# Motorcontroller.net
KiCad netlist of a schematic drawn in EAGLE
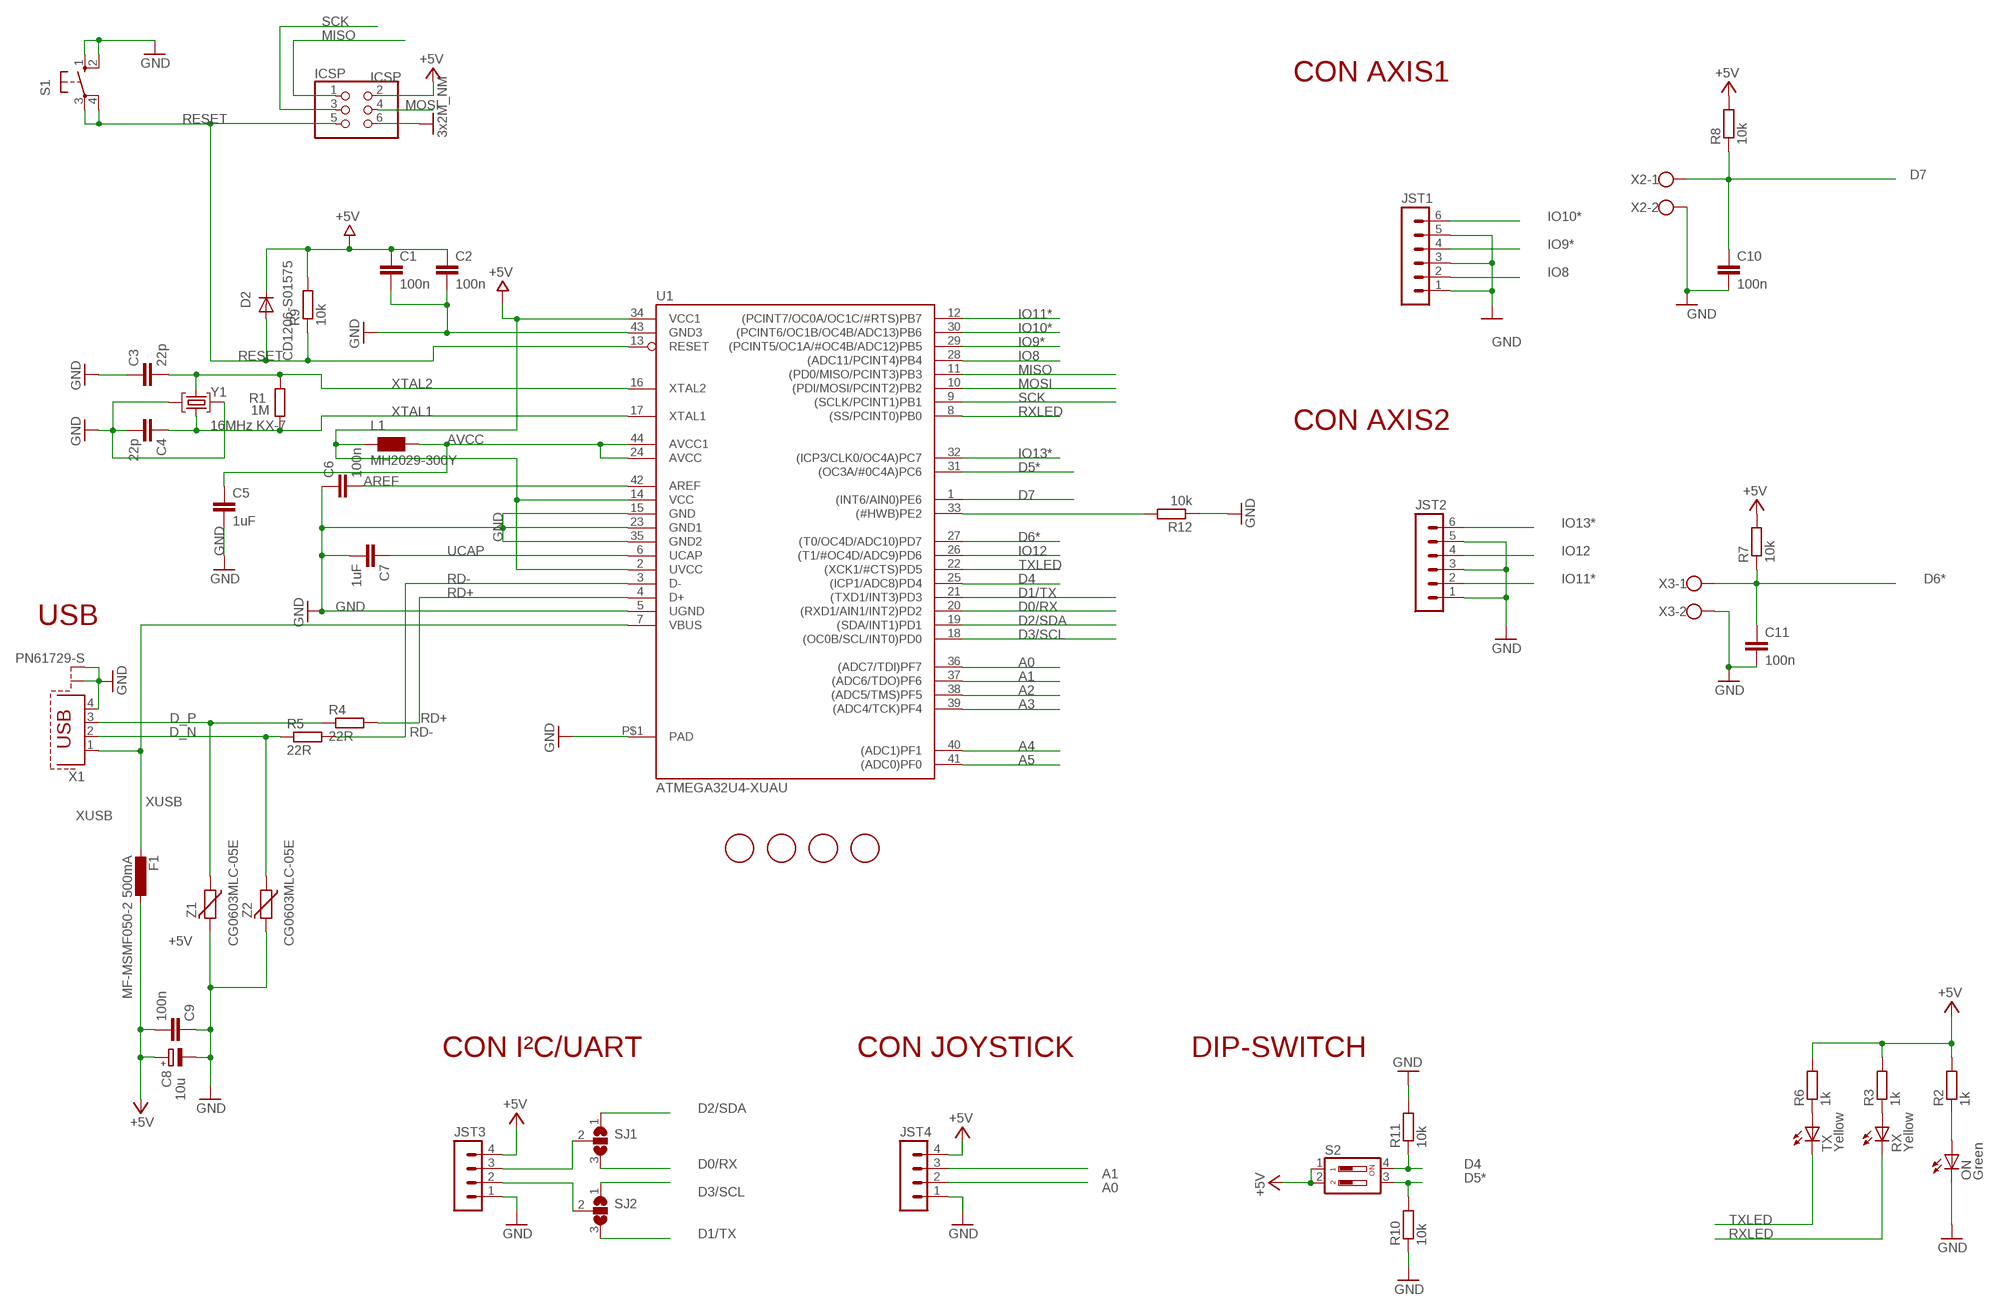
[diagram p0: schematic, sheet 1]

(export (version "E")
  (design (tool "Eeschema 10.0.6"))
  (components
    (comp (ref "C1")
      (value "100n")
      (footprint "eagle-import:C0805")
      (libsource (lib "eagle-import") (part "C-EUC0805"))
    )
    (comp (ref "C2")
      (value "100n")
      (footprint "eagle-import:C0805")
      (libsource (lib "eagle-import") (part "C-EUC0805"))
    )
    (comp (ref "C3")
      (value "22p")
      (footprint "eagle-import:C0805")
      (libsource (lib "eagle-import") (part "C-EUC0805"))
    )
    (comp (ref "C4")
      (value "22p")
      (footprint "eagle-import:C0805")
      (libsource (lib "eagle-import") (part "C-EUC0805"))
    )
    (comp (ref "C5")
      (value "1uF")
      (footprint "eagle-import:C0805")
      (libsource (lib "eagle-import") (part "C-EUC0805"))
    )
    (comp (ref "C6")
      (value "100n")
      (footprint "eagle-import:C0805")
      (libsource (lib "eagle-import") (part "C-EUC0805"))
    )
    (comp (ref "C7")
      (value "1uF")
      (footprint "eagle-import:C0805")
      (libsource (lib "eagle-import") (part "C-EUC0805"))
    )
    (comp (ref "C8")
      (value "10u")
      (footprint "eagle-import:SMC_B")
      (libsource (lib "eagle-import") (part "CPOL-EUSMCB"))
    )
    (comp (ref "C9")
      (value "100n")
      (footprint "eagle-import:C0805")
      (libsource (lib "eagle-import") (part "C-EUC0805"))
    )
    (comp (ref "C10")
      (value "100n")
      (footprint "eagle-import:C0805")
      (libsource (lib "eagle-import") (part "rcl_334_C-EUC0805"))
    )
    (comp (ref "C11")
      (value "100n")
      (footprint "eagle-import:C0805")
      (libsource (lib "eagle-import") (part "rcl_334_C-EUC0805"))
    )
    (comp (ref "D2")
      (value "CD1206-S01575")
      (footprint "eagle-import:MINIMELF")
      (libsource (lib "eagle-import") (part "DIODE-MINIMELF"))
    )
    (comp (ref "F1")
      (value "MF-MSMF050-2 500mA")
      (footprint "eagle-import:L1812")
      (libsource (lib "eagle-import") (part "L-EUL1812"))
    )
    (comp (ref "FID1")
      (value "FIDUCIALMOUNT")
      (footprint "eagle-import:FIDUCIA-MOUNT")
      (libsource (lib "eagle-import") (part "FIDUCIALMOUNT"))
    )
    (comp (ref "FID2")
      (value "FIDUCIALMOUNT")
      (footprint "eagle-import:FIDUCIA-MOUNT")
      (libsource (lib "eagle-import") (part "FIDUCIALMOUNT"))
    )
    (comp (ref "FID3")
      (value "FIDUCIALMOUNT")
      (footprint "eagle-import:FIDUCIA-MOUNT")
      (libsource (lib "eagle-import") (part "FIDUCIALMOUNT"))
    )
    (comp (ref "FID4")
      (value "FIDUCIALMOUNT")
      (footprint "eagle-import:FIDUCIA-MOUNT")
      (libsource (lib "eagle-import") (part "FIDUCIALMOUNT"))
    )
    (comp (ref "ICSP")
      (value "ICSP")
      (footprint "eagle-import:2X03")
      (libsource (lib "eagle-import") (part "PINHD-2X3"))
    )
    (comp (ref "JST1")
      (value "MA06-1")
      (footprint "eagle-import:MA06-1")
      (libsource (lib "eagle-import") (part "MA06-1"))
    )
    (comp (ref "JST2")
      (value "MA06-1")
      (footprint "eagle-import:MA06-1")
      (libsource (lib "eagle-import") (part "MA06-1"))
    )
    (comp (ref "JST3")
      (value "MA04-1")
      (footprint "eagle-import:MA04-1")
      (libsource (lib "eagle-import") (part "MA04-1"))
    )
    (comp (ref "JST4")
      (value "MA04-1")
      (footprint "eagle-import:MA04-1")
      (libsource (lib "eagle-import") (part "MA04-1"))
    )
    (comp (ref "L1")
      (value "MH2029-300Y")
      (footprint "eagle-import:0805")
      (libsource (lib "eagle-import") (part "WE-CBF_0805"))
    )
    (comp (ref "ON")
      (value "Green")
      (footprint "eagle-import:CHIPLED_0805")
      (libsource (lib "eagle-import") (part "LEDCHIPLED_0805"))
    )
    (comp (ref "R1")
      (value "1M")
      (footprint "eagle-import:R0805")
      (libsource (lib "eagle-import") (part "R-EU_R0805"))
    )
    (comp (ref "R2")
      (value "1k")
      (footprint "eagle-import:R0805")
      (libsource (lib "eagle-import") (part "rcl_334_R-EU_R0805"))
    )
    (comp (ref "R3")
      (value "1k")
      (footprint "eagle-import:R0805")
      (libsource (lib "eagle-import") (part "rcl_334_R-EU_R0805"))
    )
    (comp (ref "R4")
      (value "22R")
      (footprint "eagle-import:R0805")
      (libsource (lib "eagle-import") (part "rcl_334_R-EU_R0805"))
    )
    (comp (ref "R5")
      (value "22R")
      (footprint "eagle-import:R0805")
      (libsource (lib "eagle-import") (part "rcl_334_R-EU_R0805"))
    )
    (comp (ref "R6")
      (value "1k")
      (footprint "eagle-import:R0805")
      (libsource (lib "eagle-import") (part "rcl_334_R-EU_R0805"))
    )
    (comp (ref "R7")
      (value "10k")
      (footprint "eagle-import:R0805")
      (libsource (lib "eagle-import") (part "rcl_334_R-EU_R0805"))
    )
    (comp (ref "R8")
      (value "10k")
      (footprint "eagle-import:R0805")
      (libsource (lib "eagle-import") (part "rcl_334_R-EU_R0805"))
    )
    (comp (ref "R9")
      (value "10k")
      (footprint "eagle-import:R0805")
      (libsource (lib "eagle-import") (part "rcl_334_R-EU_R0805"))
    )
    (comp (ref "R10")
      (value "10k")
      (footprint "eagle-import:R0805")
      (libsource (lib "eagle-import") (part "rcl_334_R-EU_R0805"))
    )
    (comp (ref "R11")
      (value "10k")
      (footprint "eagle-import:R0805")
      (libsource (lib "eagle-import") (part "rcl_334_R-EU_R0805"))
    )
    (comp (ref "R12")
      (value "10k")
      (footprint "eagle-import:R0805")
      (libsource (lib "eagle-import") (part "rcl_334_R-EU_R0805"))
    )
    (comp (ref "RX")
      (value "Yellow")
      (footprint "eagle-import:CHIPLED_0805")
      (libsource (lib "eagle-import") (part "LEDCHIPLED_0805"))
    )
    (comp (ref "S1")
      (value "10-XX")
      (footprint "eagle-import:B3F-10XX")
      (fields (field (name "MPN") "B3F-1000"))
      (libsource (lib "eagle-import") (part "10-XX"))
    )
    (comp (ref "S2")
      (value "DIP02YL")
      (footprint "eagle-import:DIP02YL")
      (libsource (lib "eagle-import") (part "DIP02YL"))
    )
    (comp (ref "SJ1")
      (value "SJ2W")
      (footprint "eagle-import:SJ_2")
      (libsource (lib "eagle-import") (part "SJ2W"))
    )
    (comp (ref "SJ2")
      (value "SJ2W")
      (footprint "eagle-import:SJ_2")
      (libsource (lib "eagle-import") (part "SJ2W"))
    )
    (comp (ref "TX")
      (value "Yellow")
      (footprint "eagle-import:CHIPLED_0805")
      (libsource (lib "eagle-import") (part "LEDCHIPLED_0805"))
    )
    (comp (ref "U1")
      (value "ATMEGA32U4-XUAU")
      (footprint "eagle-import:TQFP44-PAD")
      (libsource (lib "eagle-import") (part "ATMEGA32U4-XUAU"))
    )
    (comp (ref "X1")
      (value "PN61729-S")
      (footprint "eagle-import:PN61729-S")
      (libsource (lib "eagle-import") (part "PN61729-S"))
    )
    (comp (ref "X2")
      (value "W237-102")
      (footprint "eagle-import:W237-102")
      (fields (field (name "MPN") "237-102"))
      (libsource (lib "eagle-import") (part "W237-102"))
    )
    (comp (ref "X3")
      (value "W237-102")
      (footprint "eagle-import:W237-102")
      (fields (field (name "MPN") "237-102"))
      (libsource (lib "eagle-import") (part "W237-102"))
    )
    (comp (ref "Y1")
      (value "16MHz KX-7")
      (footprint "eagle-import:CRYSTAL-3.2-2.5")
      (libsource (lib "eagle-import") (part "CRYSTAL-3.2-2.5"))
    )
    (comp (ref "Z1")
      (value "CG0603MLC-05E")
      (footprint "eagle-import:CT_CN0805")
      (libsource (lib "eagle-import") (part "VARISTORCN0805"))
    )
    (comp (ref "Z2")
      (value "CG0603MLC-05E")
      (footprint "eagle-import:CT_CN0805")
      (libsource (lib "eagle-import") (part "VARISTORCN0805"))
    )
  )
  (nets
    (net (code "1") (name "+5V") (class "Default")
      (node (ref "C1") (pin "1") (pinfunction "1_1") (pintype "passive"))
      (node (ref "C2") (pin "1") (pinfunction "1_1") (pintype "passive"))
      (node (ref "C8") (pin "+") (pinfunction "+_+") (pintype "passive"))
      (node (ref "C9") (pin "2") (pinfunction "2_2") (pintype "passive"))
      (node (ref "D2") (pin "C") (pinfunction "C_C") (pintype "passive"))
      (node (ref "F1") (pin "1") (pinfunction "1_1") (pintype "passive"))
      (node (ref "ICSP") (pin "2") (pinfunction "2_2") (pintype "passive"))
      (node (ref "JST3") (pin "4") (pinfunction "4_4") (pintype "passive"))
      (node (ref "JST4") (pin "4") (pinfunction "4_4") (pintype "passive"))
      (node (ref "L1") (pin "1") (pinfunction "1_1") (pintype "passive"))
      (node (ref "R2") (pin "2") (pinfunction "2_2") (pintype "passive"))
      (node (ref "R3") (pin "2") (pinfunction "2_2") (pintype "passive"))
      (node (ref "R6") (pin "2") (pinfunction "2_2") (pintype "passive"))
      (node (ref "R7") (pin "2") (pinfunction "2_2") (pintype "passive"))
      (node (ref "R8") (pin "2") (pinfunction "2_2") (pintype "passive"))
      (node (ref "R9") (pin "2") (pinfunction "2_2") (pintype "passive"))
      (node (ref "S2") (pin "1") (pinfunction "1_1") (pintype "passive"))
      (node (ref "S2") (pin "2") (pinfunction "2_2") (pintype "passive"))
      (node (ref "U1") (pin "14") (pinfunction "VCC_14") (pintype "power_in"))
      (node (ref "U1") (pin "2") (pinfunction "UVCC_2") (pintype "power_in"))
      (node (ref "U1") (pin "34") (pinfunction "VCC1_34") (pintype "power_in"))
    )
    (net (code "2") (name "/A0") (class "Default")
      (node (ref "JST4") (pin "2") (pinfunction "2_2") (pintype "passive"))
      (node (ref "U1") (pin "36") (pinfunction "(ADC7/TDI)PF7_36") (pintype "bidirectional"))
    )
    (net (code "3") (name "/A1") (class "Default")
      (node (ref "JST4") (pin "3") (pinfunction "3_3") (pintype "passive"))
      (node (ref "U1") (pin "37") (pinfunction "(ADC6/TDO)PF6_37") (pintype "bidirectional"))
    )
    (net (code "4") (name "/A2") (class "Default")
      (node (ref "U1") (pin "38") (pinfunction "(ADC5/TMS)PF5_38") (pintype "bidirectional"))
    )
    (net (code "5") (name "/A3") (class "Default")
      (node (ref "U1") (pin "39") (pinfunction "(ADC4/TCK)PF4_39") (pintype "bidirectional"))
    )
    (net (code "6") (name "/A4") (class "Default")
      (node (ref "U1") (pin "40") (pinfunction "(ADC1)PF1_40") (pintype "bidirectional"))
    )
    (net (code "7") (name "/A5") (class "Default")
      (node (ref "U1") (pin "41") (pinfunction "(ADC0)PF0_41") (pintype "bidirectional"))
    )
    (net (code "8") (name "/AREF") (class "Default")
      (node (ref "C6") (pin "2") (pinfunction "2_2") (pintype "passive"))
      (node (ref "U1") (pin "42") (pinfunction "AREF_42") (pintype "power_in"))
    )
    (net (code "9") (name "/AVCC") (class "Default")
      (node (ref "C5") (pin "1") (pinfunction "1_1") (pintype "passive"))
      (node (ref "L1") (pin "2") (pinfunction "2_2") (pintype "passive"))
      (node (ref "U1") (pin "24") (pinfunction "AVCC_24") (pintype "power_in"))
      (node (ref "U1") (pin "44") (pinfunction "AVCC1_44") (pintype "power_in"))
    )
    (net (code "10") (name "/D0{slash}RX") (class "Default")
      (node (ref "SJ1") (pin "3") (pinfunction "3_3") (pintype "passive"))
      (node (ref "U1") (pin "20") (pinfunction "(RXD1/AIN1/INT2)PD2_20") (pintype "bidirectional"))
    )
    (net (code "11") (name "/D1{slash}TX") (class "Default")
      (node (ref "SJ2") (pin "3") (pinfunction "3_3") (pintype "passive"))
      (node (ref "U1") (pin "21") (pinfunction "(TXD1/INT3)PD3_21") (pintype "bidirectional"))
    )
    (net (code "12") (name "/D2{slash}SDA") (class "Default")
      (node (ref "SJ1") (pin "1") (pinfunction "1_1") (pintype "passive"))
      (node (ref "U1") (pin "19") (pinfunction "(SDA/INT1)PD1_19") (pintype "bidirectional"))
    )
    (net (code "13") (name "/D3{slash}SCL") (class "Default")
      (node (ref "SJ2") (pin "1") (pinfunction "1_1") (pintype "passive"))
      (node (ref "U1") (pin "18") (pinfunction "(OC0B/SCL/INT0)PD0_18") (pintype "bidirectional"))
    )
    (net (code "14") (name "/D4") (class "Default")
      (node (ref "R11") (pin "1") (pinfunction "1_1") (pintype "passive"))
      (node (ref "S2") (pin "4") (pinfunction "4_4") (pintype "passive"))
      (node (ref "U1") (pin "25") (pinfunction "(ICP1/ADC8)PD4_25") (pintype "bidirectional"))
    )
    (net (code "15") (name "/D5*") (class "Default")
      (node (ref "R10") (pin "2") (pinfunction "2_2") (pintype "passive"))
      (node (ref "S2") (pin "3") (pinfunction "3_3") (pintype "passive"))
      (node (ref "U1") (pin "31") (pinfunction "(OC3A/#0C4A)PC6_31") (pintype "bidirectional"))
    )
    (net (code "16") (name "/D6*") (class "Default")
      (node (ref "C11") (pin "1") (pinfunction "1_1") (pintype "passive"))
      (node (ref "R7") (pin "1") (pinfunction "1_1") (pintype "passive"))
      (node (ref "U1") (pin "27") (pinfunction "(T0/OC4D/ADC10)PD7_27") (pintype "bidirectional"))
      (node (ref "X3") (pin "1") (pinfunction "KL_1") (pintype "passive"))
    )
    (net (code "17") (name "/D7") (class "Default")
      (node (ref "C10") (pin "1") (pinfunction "1_1") (pintype "passive"))
      (node (ref "R8") (pin "1") (pinfunction "1_1") (pintype "passive"))
      (node (ref "U1") (pin "1") (pinfunction "(INT6/AIN0)PE6_1") (pintype "bidirectional"))
      (node (ref "X2") (pin "1") (pinfunction "KL_1") (pintype "passive"))
    )
    (net (code "18") (name "/D_N") (class "Default")
      (node (ref "R5") (pin "1") (pinfunction "1_1") (pintype "passive"))
      (node (ref "X1") (pin "2") (pinfunction "2_2") (pintype "passive"))
      (node (ref "Z2") (pin "1") (pinfunction "1_1") (pintype "passive"))
    )
    (net (code "19") (name "/D_P") (class "Default")
      (node (ref "R4") (pin "1") (pinfunction "1_1") (pintype "passive"))
      (node (ref "X1") (pin "3") (pinfunction "3_3") (pintype "passive"))
      (node (ref "Z1") (pin "1") (pinfunction "1_1") (pintype "passive"))
    )
    (net (code "20") (name "/IO8") (class "Default")
      (node (ref "JST1") (pin "2") (pinfunction "2_2") (pintype "passive"))
      (node (ref "U1") (pin "28") (pinfunction "(ADC11/PCINT4)PB4_28") (pintype "bidirectional"))
    )
    (net (code "21") (name "/IO9*") (class "Default")
      (node (ref "JST1") (pin "4") (pinfunction "4_4") (pintype "passive"))
      (node (ref "U1") (pin "29") (pinfunction "(PCINT5/OC1A/#OC4B/ADC12)PB5_29") (pintype "bidirectional"))
    )
    (net (code "22") (name "/IO10*") (class "Default")
      (node (ref "JST1") (pin "6") (pinfunction "6_6") (pintype "passive"))
      (node (ref "U1") (pin "30") (pinfunction "(PCINT6/OC1B/OC4B/ADC13)PB6_30") (pintype "bidirectional"))
    )
    (net (code "23") (name "/IO11*") (class "Default")
      (node (ref "JST2") (pin "2") (pinfunction "2_2") (pintype "passive"))
      (node (ref "U1") (pin "12") (pinfunction "(PCINT7/OC0A/OC1C/#RTS)PB7_12") (pintype "bidirectional"))
    )
    (net (code "24") (name "/IO12") (class "Default")
      (node (ref "JST2") (pin "4") (pinfunction "4_4") (pintype "passive"))
      (node (ref "U1") (pin "26") (pinfunction "(T1/#OC4D/ADC9)PD6_26") (pintype "bidirectional"))
    )
    (net (code "25") (name "/IO13*") (class "Default")
      (node (ref "JST2") (pin "6") (pinfunction "6_6") (pintype "passive"))
      (node (ref "U1") (pin "32") (pinfunction "(ICP3/CLK0/OC4A)PC7_32") (pintype "bidirectional"))
    )
    (net (code "26") (name "/MISO") (class "Default")
      (node (ref "ICSP") (pin "1") (pinfunction "1_1") (pintype "passive"))
      (node (ref "U1") (pin "11") (pinfunction "(PD0/MISO/PCINT3)PB3_11") (pintype "bidirectional"))
    )
    (net (code "27") (name "/MOSI") (class "Default")
      (node (ref "ICSP") (pin "4") (pinfunction "4_4") (pintype "passive"))
      (node (ref "U1") (pin "10") (pinfunction "(PDI/MOSI/PCINT2)PB2_10") (pintype "bidirectional"))
    )
    (net (code "28") (name "/RD+") (class "Default")
      (node (ref "R4") (pin "2") (pinfunction "2_2") (pintype "passive"))
      (node (ref "U1") (pin "4") (pinfunction "D+_4") (pintype "bidirectional"))
    )
    (net (code "29") (name "/RD-") (class "Default")
      (node (ref "R5") (pin "2") (pinfunction "2_2") (pintype "passive"))
      (node (ref "U1") (pin "3") (pinfunction "D-_3") (pintype "bidirectional"))
    )
    (net (code "30") (name "/RESET") (class "Default")
      (node (ref "D2") (pin "A") (pinfunction "A_A") (pintype "passive"))
      (node (ref "ICSP") (pin "5") (pinfunction "5_5") (pintype "passive"))
      (node (ref "R9") (pin "1") (pinfunction "1_1") (pintype "passive"))
      (node (ref "S1") (pin "3") (pinfunction "P_3") (pintype "passive"))
      (node (ref "S1") (pin "4") (pinfunction "P1_4") (pintype "passive"))
      (node (ref "U1") (pin "13") (pinfunction "RESET_13") (pintype "input"))
    )
    (net (code "31") (name "/RXLED") (class "Default")
      (node (ref "RX") (pin "C") (pinfunction "C_C") (pintype "passive"))
      (node (ref "U1") (pin "8") (pinfunction "(SS/PCINT0)PB0_8") (pintype "bidirectional"))
    )
    (net (code "32") (name "/SCK") (class "Default")
      (node (ref "ICSP") (pin "3") (pinfunction "3_3") (pintype "passive"))
      (node (ref "U1") (pin "9") (pinfunction "(SCLK/PCINT1)PB1_9") (pintype "bidirectional"))
    )
    (net (code "33") (name "/TXLED") (class "Default")
      (node (ref "TX") (pin "C") (pinfunction "C_C") (pintype "passive"))
      (node (ref "U1") (pin "22") (pinfunction "(XCK1/#CTS)PD5_22") (pintype "bidirectional"))
    )
    (net (code "34") (name "/UCAP") (class "Default")
      (node (ref "C7") (pin "1") (pinfunction "1_1") (pintype "passive"))
      (node (ref "U1") (pin "6") (pinfunction "UCAP_6") (pintype "passive"))
    )
    (net (code "35") (name "/XTAL1") (class "Default")
      (node (ref "C4") (pin "1") (pinfunction "1_1") (pintype "passive"))
      (node (ref "R1") (pin "1") (pinfunction "1_1") (pintype "passive"))
      (node (ref "U1") (pin "17") (pinfunction "XTAL1_17") (pintype "bidirectional"))
      (node (ref "Y1") (pin "1") (pinfunction "C1_1") (pintype "passive"))
    )
    (net (code "36") (name "/XTAL2") (class "Default")
      (node (ref "C3") (pin "2") (pinfunction "2_2") (pintype "passive"))
      (node (ref "R1") (pin "2") (pinfunction "2_2") (pintype "passive"))
      (node (ref "U1") (pin "16") (pinfunction "XTAL2_16") (pintype "bidirectional"))
      (node (ref "Y1") (pin "3") (pinfunction "C2_3") (pintype "passive"))
    )
    (net (code "37") (name "/XUSB") (class "Default")
      (node (ref "F1") (pin "2") (pinfunction "2_2") (pintype "passive"))
      (node (ref "U1") (pin "7") (pinfunction "VBUS_7") (pintype "input"))
      (node (ref "X1") (pin "1") (pinfunction "1_1") (pintype "passive"))
    )
    (net (code "38") (name "3x2M_NM") (class "Default")
      (node (ref "C1") (pin "2") (pinfunction "2_2") (pintype "passive"))
      (node (ref "C10") (pin "2") (pinfunction "2_2") (pintype "passive"))
      (node (ref "C11") (pin "2") (pinfunction "2_2") (pintype "passive"))
      (node (ref "C2") (pin "2") (pinfunction "2_2") (pintype "passive"))
      (node (ref "C3") (pin "1") (pinfunction "1_1") (pintype "passive"))
      (node (ref "C4") (pin "2") (pinfunction "2_2") (pintype "passive"))
      (node (ref "C5") (pin "2") (pinfunction "2_2") (pintype "passive"))
      (node (ref "C6") (pin "1") (pinfunction "1_1") (pintype "passive"))
      (node (ref "C7") (pin "2") (pinfunction "2_2") (pintype "passive"))
      (node (ref "C8") (pin "-") (pinfunction "-_-") (pintype "passive"))
      (node (ref "C9") (pin "1") (pinfunction "1_1") (pintype "passive"))
      (node (ref "ICSP") (pin "6") (pinfunction "6_6") (pintype "passive"))
      (node (ref "JST1") (pin "1") (pinfunction "1_1") (pintype "passive"))
      (node (ref "JST1") (pin "3") (pinfunction "3_3") (pintype "passive"))
      (node (ref "JST1") (pin "5") (pinfunction "5_5") (pintype "passive"))
      (node (ref "JST2") (pin "1") (pinfunction "1_1") (pintype "passive"))
      (node (ref "JST2") (pin "3") (pinfunction "3_3") (pintype "passive"))
      (node (ref "JST2") (pin "5") (pinfunction "5_5") (pintype "passive"))
      (node (ref "JST3") (pin "1") (pinfunction "1_1") (pintype "passive"))
      (node (ref "JST4") (pin "1") (pinfunction "1_1") (pintype "passive"))
      (node (ref "ON") (pin "C") (pinfunction "C_C") (pintype "passive"))
      (node (ref "R10") (pin "1") (pinfunction "1_1") (pintype "passive"))
      (node (ref "R11") (pin "2") (pinfunction "2_2") (pintype "passive"))
      (node (ref "R12") (pin "1") (pinfunction "1_1") (pintype "passive"))
      (node (ref "S1") (pin "1") (pinfunction "S_1") (pintype "passive"))
      (node (ref "S1") (pin "2") (pinfunction "S1_2") (pintype "passive"))
      (node (ref "U1") (pin "15") (pinfunction "GND_15") (pintype "power_in"))
      (node (ref "U1") (pin "23") (pinfunction "GND1_23") (pintype "power_in"))
      (node (ref "U1") (pin "35") (pinfunction "GND2_35") (pintype "power_in"))
      (node (ref "U1") (pin "43") (pinfunction "GND3_43") (pintype "power_in"))
      (node (ref "U1") (pin "5") (pinfunction "UGND_5") (pintype "power_in"))
      (node (ref "U1") (pin "P$1") (pinfunction "PAD_P$1") (pintype "power_in"))
      (node (ref "X1") (pin "4") (pinfunction "4_4") (pintype "passive"))
      (node (ref "X1") (pin "S1") (pinfunction "S1_S1") (pintype "passive"))
      (node (ref "X1") (pin "S2") (pinfunction "S2_S2") (pintype "passive"))
      (node (ref "X2") (pin "2") (pinfunction "KL_2") (pintype "passive"))
      (node (ref "X3") (pin "2") (pinfunction "KL_2") (pintype "passive"))
      (node (ref "Y1") (pin "2") (pinfunction "GND_2") (pintype "passive"))
      (node (ref "Y1") (pin "4") (pinfunction "GND_4") (pintype "passive"))
      (node (ref "Z1") (pin "2") (pinfunction "2_2") (pintype "passive"))
      (node (ref "Z2") (pin "2") (pinfunction "2_2") (pintype "passive"))
    )
    (net (code "39") (name "Net-(JST3-Pad2)") (class "Default")
      (node (ref "JST3") (pin "2") (pinfunction "2_2") (pintype "passive"))
      (node (ref "SJ2") (pin "2") (pinfunction "2_2") (pintype "passive"))
    )
    (net (code "40") (name "Net-(JST3-Pad3)") (class "Default")
      (node (ref "JST3") (pin "3") (pinfunction "3_3") (pintype "passive"))
      (node (ref "SJ1") (pin "2") (pinfunction "2_2") (pintype "passive"))
    )
    (net (code "41") (name "Net-(ON-PadA)") (class "Default")
      (node (ref "ON") (pin "A") (pinfunction "A_A") (pintype "passive"))
      (node (ref "R2") (pin "1") (pinfunction "1_1") (pintype "passive"))
    )
    (net (code "42") (name "Net-(R3-Pad1)") (class "Default")
      (node (ref "R3") (pin "1") (pinfunction "1_1") (pintype "passive"))
      (node (ref "RX") (pin "A") (pinfunction "A_A") (pintype "passive"))
    )
    (net (code "43") (name "Net-(R6-Pad1)") (class "Default")
      (node (ref "R6") (pin "1") (pinfunction "1_1") (pintype "passive"))
      (node (ref "TX") (pin "A") (pinfunction "A_A") (pintype "passive"))
    )
    (net (code "44") (name "Net-(U1-(#HWB)PE2)") (class "Default")
      (node (ref "R12") (pin "2") (pinfunction "2_2") (pintype "passive"))
      (node (ref "U1") (pin "33") (pinfunction "(#HWB)PE2_33") (pintype "bidirectional"))
    )
  )
)
